# Button_-_Single.net
KiCad netlist of a schematic drawn in EAGLE
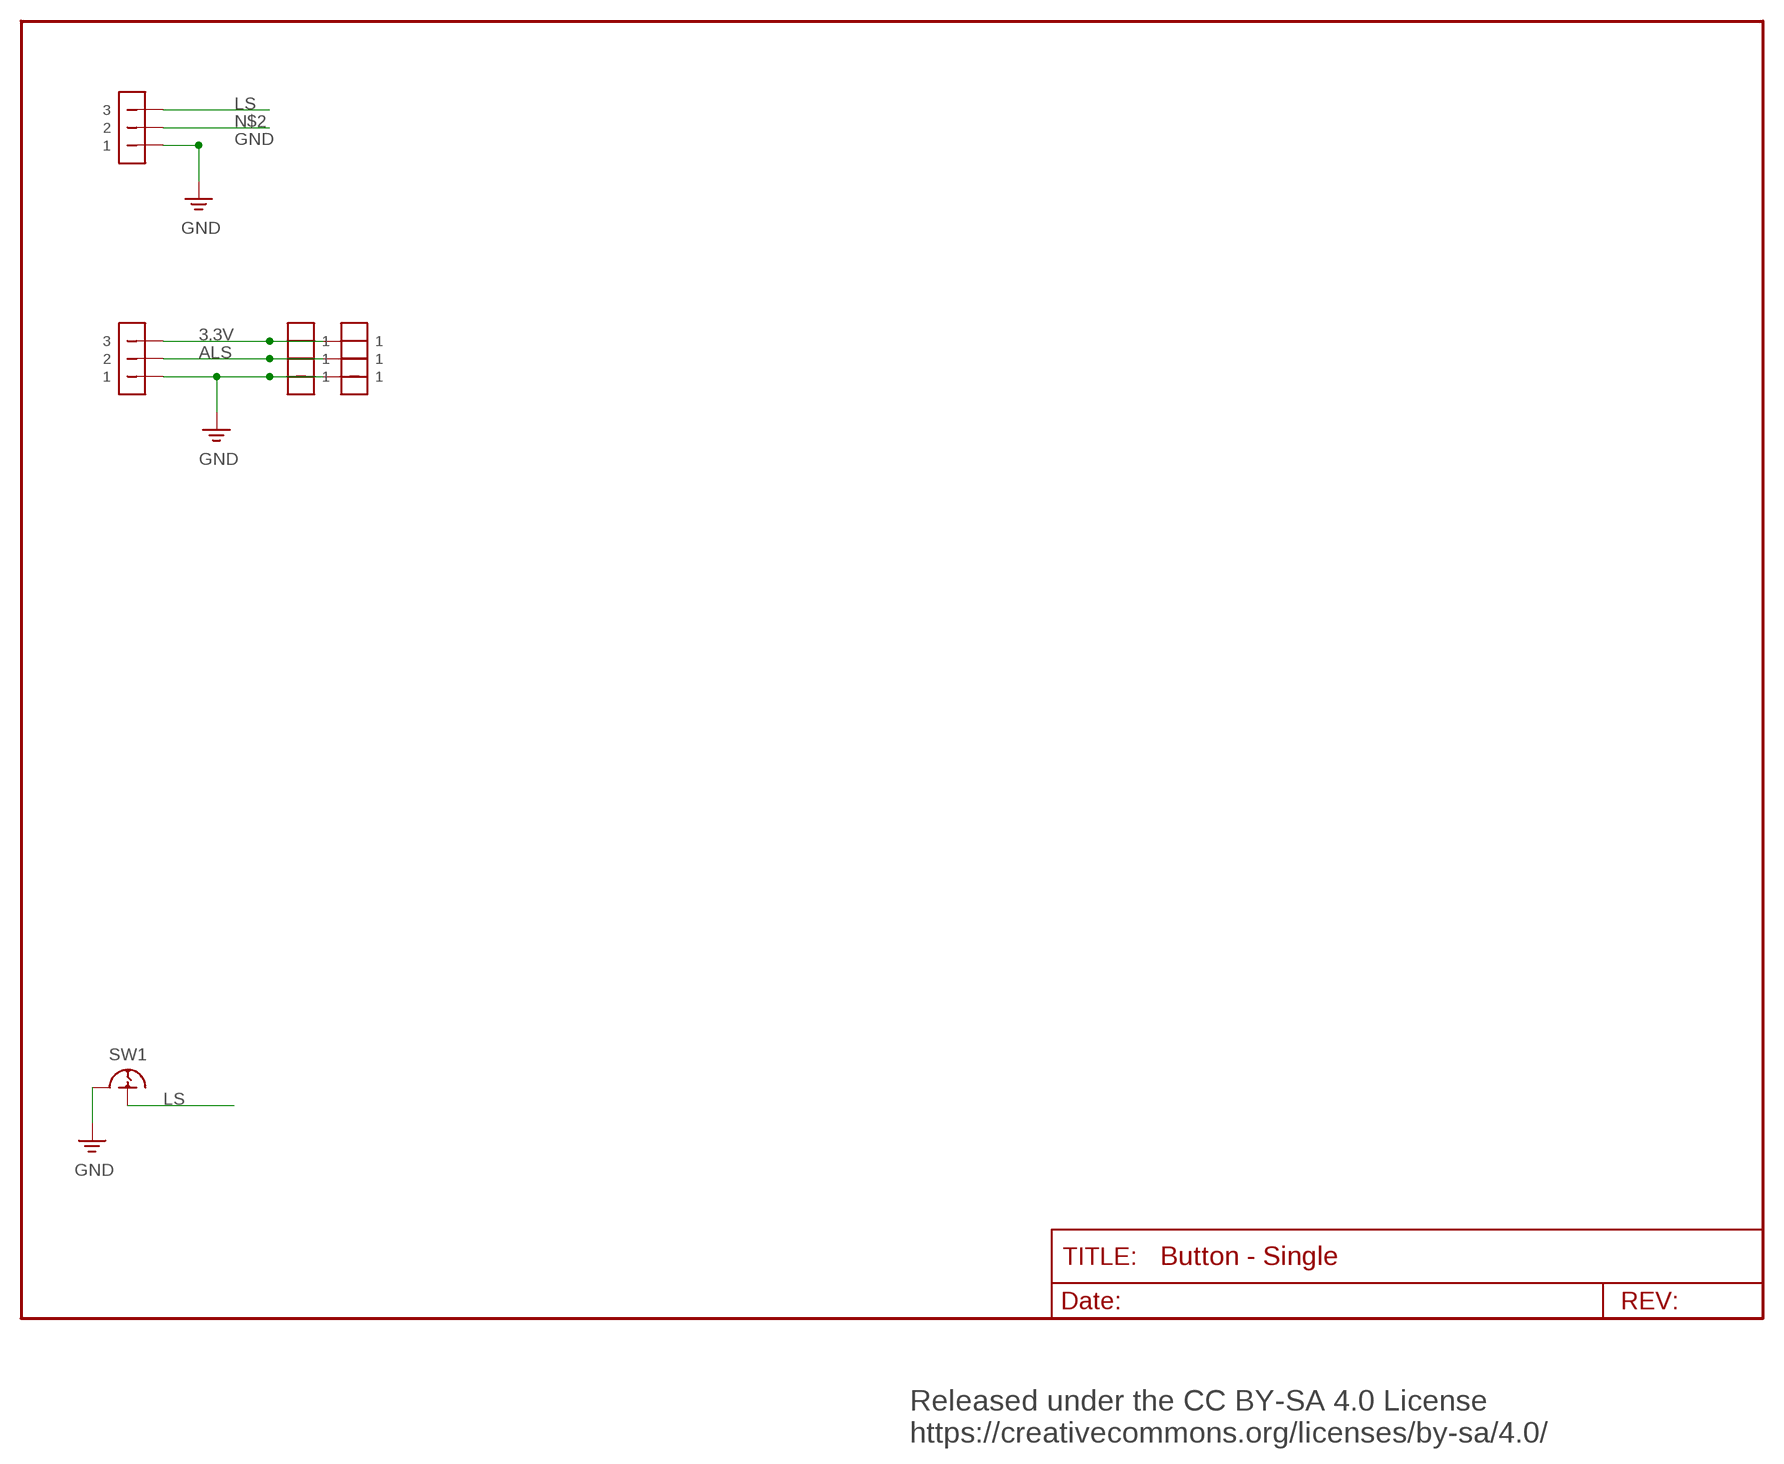
[diagram p0: schematic, sheet 1]

(export (version "E")
  (design (tool "Eeschema 10.0.6"))
  (components
    (comp (ref "SW1")
      (value "U12390")
      (footprint "eagle-import:UFTCGX12")
      (libsource (lib "eagle-import") (part "U12390"))
    )
    (comp (ref "U$1")
      (value "M03")
      (footprint "eagle-import:M03")
      (libsource (lib "eagle-import") (part "M03"))
    )
    (comp (ref "U$2")
      (value "M03")
      (footprint "eagle-import:M03")
      (libsource (lib "eagle-import") (part "M03"))
    )
    (comp (ref "U$3")
      (value "S01-4MM")
      (footprint "eagle-import:S01-4MM")
      (libsource (lib "eagle-import") (part "S01-4MM"))
    )
    (comp (ref "U$4")
      (value "S01-4MM")
      (footprint "eagle-import:S01-4MM")
      (libsource (lib "eagle-import") (part "S01-4MM"))
    )
    (comp (ref "U$5")
      (value "S01-4MM")
      (footprint "eagle-import:S01-4MM")
      (libsource (lib "eagle-import") (part "S01-4MM"))
    )
    (comp (ref "U$6")
      (value "S01-4MM")
      (footprint "eagle-import:S01-4MM")
      (libsource (lib "eagle-import") (part "S01-4MM"))
    )
    (comp (ref "U$7")
      (value "S01-4MM")
      (footprint "eagle-import:S01-4MM")
      (libsource (lib "eagle-import") (part "S01-4MM"))
    )
    (comp (ref "U$8")
      (value "S01-4MM")
      (footprint "eagle-import:S01-4MM")
      (libsource (lib "eagle-import") (part "S01-4MM"))
    )
  )
  (nets
    (net (code "1") (name "/3.3V") (class "Default")
      (node (ref "U$1") (pin "3") (pinfunction "3_3") (pintype "bidirectional"))
      (node (ref "U$3") (pin "P$1") (pinfunction "1_P$1") (pintype "bidirectional"))
      (node (ref "U$6") (pin "P$1") (pinfunction "1_P$1") (pintype "bidirectional"))
    )
    (net (code "2") (name "/ALS") (class "Default")
      (node (ref "U$1") (pin "2") (pinfunction "2_2") (pintype "bidirectional"))
      (node (ref "U$4") (pin "P$1") (pinfunction "1_P$1") (pintype "bidirectional"))
      (node (ref "U$7") (pin "P$1") (pinfunction "1_P$1") (pintype "bidirectional"))
    )
    (net (code "3") (name "/LS") (class "Default")
      (node (ref "SW1") (pin "SIG") (pinfunction "SIG_SIG") (pintype "bidirectional"))
      (node (ref "U$2") (pin "3") (pinfunction "3_3") (pintype "bidirectional"))
    )
    (net (code "4") (name "/N$2") (class "Default")
      (node (ref "U$2") (pin "2") (pinfunction "2_2") (pintype "bidirectional"))
    )
    (net (code "5") (name "GND") (class "Default")
      (node (ref "SW1") (pin "GND") (pinfunction "GND_GND") (pintype "bidirectional"))
      (node (ref "U$1") (pin "1") (pinfunction "1_1") (pintype "bidirectional"))
      (node (ref "U$2") (pin "1") (pinfunction "1_1") (pintype "bidirectional"))
      (node (ref "U$5") (pin "P$1") (pinfunction "1_P$1") (pintype "bidirectional"))
      (node (ref "U$8") (pin "P$1") (pinfunction "1_P$1") (pintype "bidirectional"))
    )
  )
)
